# GPSModule.net
KiCad netlist of a schematic drawn in Altium Designer
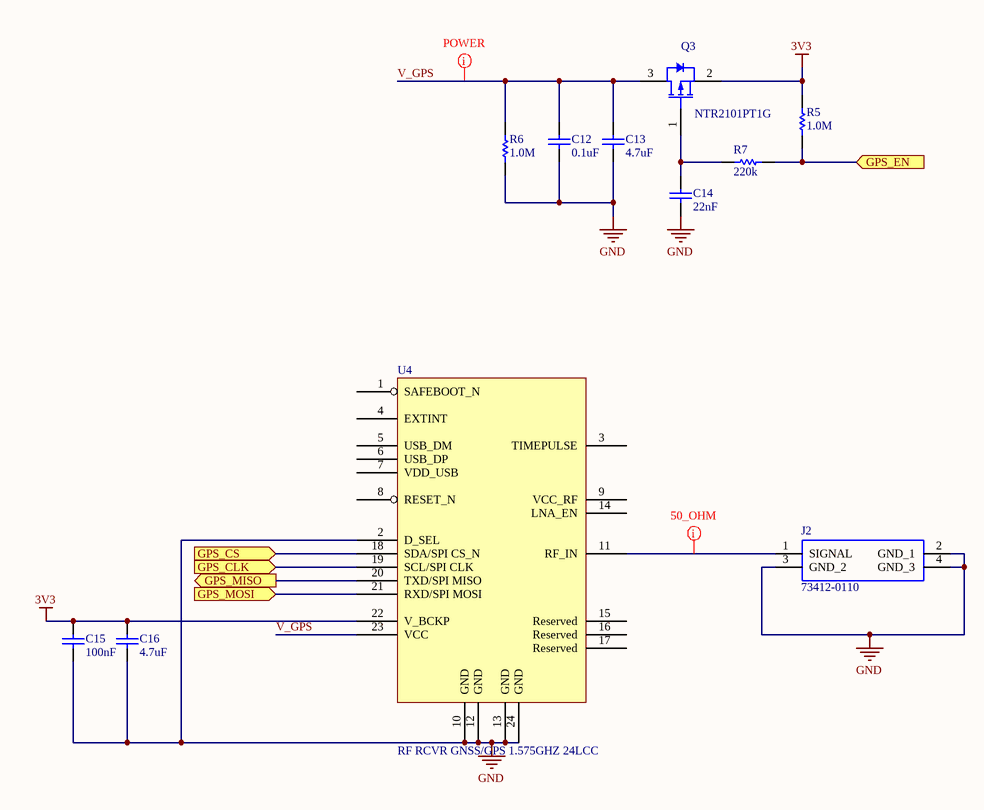
[diagram p0: GPSModule.SchDoc]

(export (version "E")
  (design (tool "Eeschema 10.0.6"))
  (components
    (comp (ref "C12")
      (value "0.1uF")
      (footprint "0402cap")
      (description "0402 Ceramic Chip Capacitor - Standard")
      (fields (field (name "Comment") "C0402"))
      (libsource (lib "lib-Standard") (part "C0402"))
    )
    (comp (ref "C13")
      (value "4.7uF")
      (footprint "0603CAP")
      (description "0603 Ceramic Chip Capacitor - Standard")
      (fields (field (name "Comment") "C0603"))
      (libsource (lib "Standard Components") (part "C0603"))
    )
    (comp (ref "C14")
      (value "22nF")
      (footprint "0402cap")
      (description "0402 Ceramic Chip Capacitor - Standard")
      (fields (field (name "Comment") "C0402"))
      (libsource (lib "lib-Standard") (part "C0402"))
    )
    (comp (ref "C15")
      (value "100nF")
      (footprint "0402cap")
      (description "0402 Ceramic Chip Capacitor - Standard")
      (fields (field (name "Comment") "C0402"))
      (libsource (lib "lib-Standard") (part "C0402"))
    )
    (comp (ref "C16")
      (value "4.7uF")
      (footprint "0603CAP")
      (description "0603 Ceramic Chip Capacitor - Standard")
      (fields (field (name "Comment") "C0603"))
      (libsource (lib "Standard Components") (part "C0603"))
    )
    (comp (ref "J2")
      (value "73412-0110")
      (footprint "73412-0110")
      (description "50 Ohms, MCRF, PCB Vertical Jack Receptacle, SMT, 1.25mm Mounted Height")
      (fields (field (name "RS PART NUMBER") "1676350") (field (name "MOUSER PART NUMBER") "538-73412-0110"))
      (libsource (lib "lib-Connectors") (part "73412-0110"))
    )
    (comp (ref "Q3")
      (value "NTR2101PT1G")
      (footprint "ONSC-SOT-23-3-318-08_V")
      (description "Small Signal MOSFET, -8 V, -3.7 A, Single P-Channel, 3-Pin SOT-23, Pb-Free, Tape and Reel")
      (libsource (lib "ON Semi MOSFETs") (part "NTR2101PT1G"))
    )
    (comp (ref "R5")
      (value "1.0M")
      (footprint "0402RES")
      (description "0402 Chip Resistor - Standard")
      (fields (field (name "Comment") "R0402"))
      (libsource (lib "lib-Standard") (part "R0402"))
    )
    (comp (ref "R6")
      (value "1.0M")
      (footprint "0402RES")
      (description "0402 Chip Resistor - Standard")
      (fields (field (name "Comment") "R0402"))
      (libsource (lib "lib-Standard") (part "R0402"))
    )
    (comp (ref "R7")
      (value "220k")
      (footprint "0402RES")
      (description "0402 Chip Resistor - Standard")
      (fields (field (name "Comment") "R0402"))
      (libsource (lib "lib-Standard") (part "R0402"))
    )
    (comp (ref "U4")
      (value "RF RCVR GNSS/GPS 1.575GHZ 24LCC")
      (footprint "NEO-M8N-0")
      (description "Concurrent GNSS LCC module, TCXO, Flash, SAW, LNA")
      (libsource (lib "lib-IC_RF") (part "NEO-M8N-0"))
    )
  )
  (nets
    (net (code "1") (name "/GPS_CLK") (class "Default")
      (node (ref "U4") (pin "19") (pinfunction "SCL/SPI_CLK_19") (pintype "passive"))
    )
    (net (code "2") (name "/GPS_CS") (class "Default")
      (node (ref "U4") (pin "18") (pinfunction "SDA/SPI_CS_N_18") (pintype "passive"))
    )
    (net (code "3") (name "/GPS_EN") (class "Default")
      (node (ref "R5") (pin "1") (pinfunction "1_1") (pintype "passive"))
      (node (ref "R7") (pin "1") (pinfunction "1_1") (pintype "passive"))
    )
    (net (code "4") (name "/GPS_MISO") (class "Default")
      (node (ref "U4") (pin "20") (pinfunction "TXD/SPI_MISO_20") (pintype "passive"))
    )
    (net (code "5") (name "/GPS_MOSI") (class "Default")
      (node (ref "U4") (pin "21") (pinfunction "RXD/SPI_MOSI_21") (pintype "passive"))
    )
    (net (code "6") (name "/V_GPS") (class "Default")
      (node (ref "C12") (pin "2") (pinfunction "2_2") (pintype "passive"))
      (node (ref "C13") (pin "2") (pinfunction "2_2") (pintype "passive"))
      (node (ref "Q3") (pin "3") (pinfunction "D_3") (pintype "passive"))
      (node (ref "R6") (pin "2") (pinfunction "2_2") (pintype "passive"))
      (node (ref "U4") (pin "23") (pinfunction "VCC_23") (pintype "passive"))
    )
    (net (code "7") (name "3V3") (class "Default")
      (node (ref "C15") (pin "2") (pinfunction "2_2") (pintype "passive"))
      (node (ref "C16") (pin "2") (pinfunction "2_2") (pintype "passive"))
      (node (ref "Q3") (pin "2") (pinfunction "S_2") (pintype "passive"))
      (node (ref "R5") (pin "2") (pinfunction "2_2") (pintype "passive"))
      (node (ref "U4") (pin "22") (pinfunction "V_BCKP_22") (pintype "passive"))
    )
    (net (code "8") (name "GND") (class "Default")
      (node (ref "C12") (pin "1") (pinfunction "1_1") (pintype "passive"))
      (node (ref "C13") (pin "1") (pinfunction "1_1") (pintype "passive"))
      (node (ref "C14") (pin "1") (pinfunction "1_1") (pintype "passive"))
      (node (ref "C15") (pin "1") (pinfunction "1_1") (pintype "passive"))
      (node (ref "C16") (pin "1") (pinfunction "1_1") (pintype "passive"))
      (node (ref "J2") (pin "2") (pinfunction "GND_1_2") (pintype "passive"))
      (node (ref "J2") (pin "3") (pinfunction "GND_2_3") (pintype "passive"))
      (node (ref "J2") (pin "4") (pinfunction "GND_3_4") (pintype "passive"))
      (node (ref "R6") (pin "1") (pinfunction "1_1") (pintype "passive"))
      (node (ref "U4") (pin "10") (pinfunction "GND_10") (pintype "passive"))
      (node (ref "U4") (pin "12") (pinfunction "GND_12") (pintype "passive"))
      (node (ref "U4") (pin "13") (pinfunction "GND_13") (pintype "passive"))
      (node (ref "U4") (pin "2") (pinfunction "D_SEL_2") (pintype "passive"))
      (node (ref "U4") (pin "24") (pinfunction "GND_24") (pintype "passive"))
    )
    (net (code "9") (name "Net-(J2-SIGNAL)") (class "Default")
      (node (ref "J2") (pin "1") (pinfunction "SIGNAL_1") (pintype "passive"))
      (node (ref "U4") (pin "11") (pinfunction "RF_IN_11") (pintype "passive"))
    )
    (net (code "10") (name "Net-(Q3-G)") (class "Default")
      (node (ref "C14") (pin "2") (pinfunction "2_2") (pintype "passive"))
      (node (ref "Q3") (pin "1") (pinfunction "G_1") (pintype "passive"))
      (node (ref "R7") (pin "2") (pinfunction "2_2") (pintype "passive"))
    )
    (net (code "11") (name "unconnected-(U4-EXTINT-Pad4)") (class "Default")
      (node (ref "U4") (pin "4") (pinfunction "EXTINT_4") (pintype "passive"))
    )
    (net (code "12") (name "unconnected-(U4-LNA_EN-Pad14)") (class "Default")
      (node (ref "U4") (pin "14") (pinfunction "LNA_EN_14") (pintype "passive"))
    )
    (net (code "13") (name "unconnected-(U4-RESET_N-Pad8)") (class "Default")
      (node (ref "U4") (pin "8") (pinfunction "RESET_N_8") (pintype "passive"))
    )
    (net (code "14") (name "unconnected-(U4-Reserved-Pad15)") (class "Default")
      (node (ref "U4") (pin "15") (pinfunction "Reserved_15") (pintype "passive"))
    )
    (net (code "15") (name "unconnected-(U4-Reserved-Pad16)") (class "Default")
      (node (ref "U4") (pin "16") (pinfunction "Reserved_16") (pintype "passive"))
    )
    (net (code "16") (name "unconnected-(U4-Reserved-Pad17)") (class "Default")
      (node (ref "U4") (pin "17") (pinfunction "Reserved_17") (pintype "passive"))
    )
    (net (code "17") (name "unconnected-(U4-SAFEBOOT_N-Pad1)") (class "Default")
      (node (ref "U4") (pin "1") (pinfunction "SAFEBOOT_N_1") (pintype "passive"))
    )
    (net (code "18") (name "unconnected-(U4-TIMEPULSE-Pad3)") (class "Default")
      (node (ref "U4") (pin "3") (pinfunction "TIMEPULSE_3") (pintype "passive"))
    )
    (net (code "19") (name "unconnected-(U4-USB_DM-Pad5)") (class "Default")
      (node (ref "U4") (pin "5") (pinfunction "USB_DM_5") (pintype "passive"))
    )
    (net (code "20") (name "unconnected-(U4-USB_DP-Pad6)") (class "Default")
      (node (ref "U4") (pin "6") (pinfunction "USB_DP_6") (pintype "passive"))
    )
    (net (code "21") (name "unconnected-(U4-VCC_RF-Pad9)") (class "Default")
      (node (ref "U4") (pin "9") (pinfunction "VCC_RF_9") (pintype "passive"))
    )
    (net (code "22") (name "unconnected-(U4-VDD_USB-Pad7)") (class "Default")
      (node (ref "U4") (pin "7") (pinfunction "VDD_USB_7") (pintype "passive"))
    )
  )
)
